# EasyEDAproject_AngstromIO_Mini_Devboard_.net
KiCad netlist of a schematic drawn in EasyEDA Pro
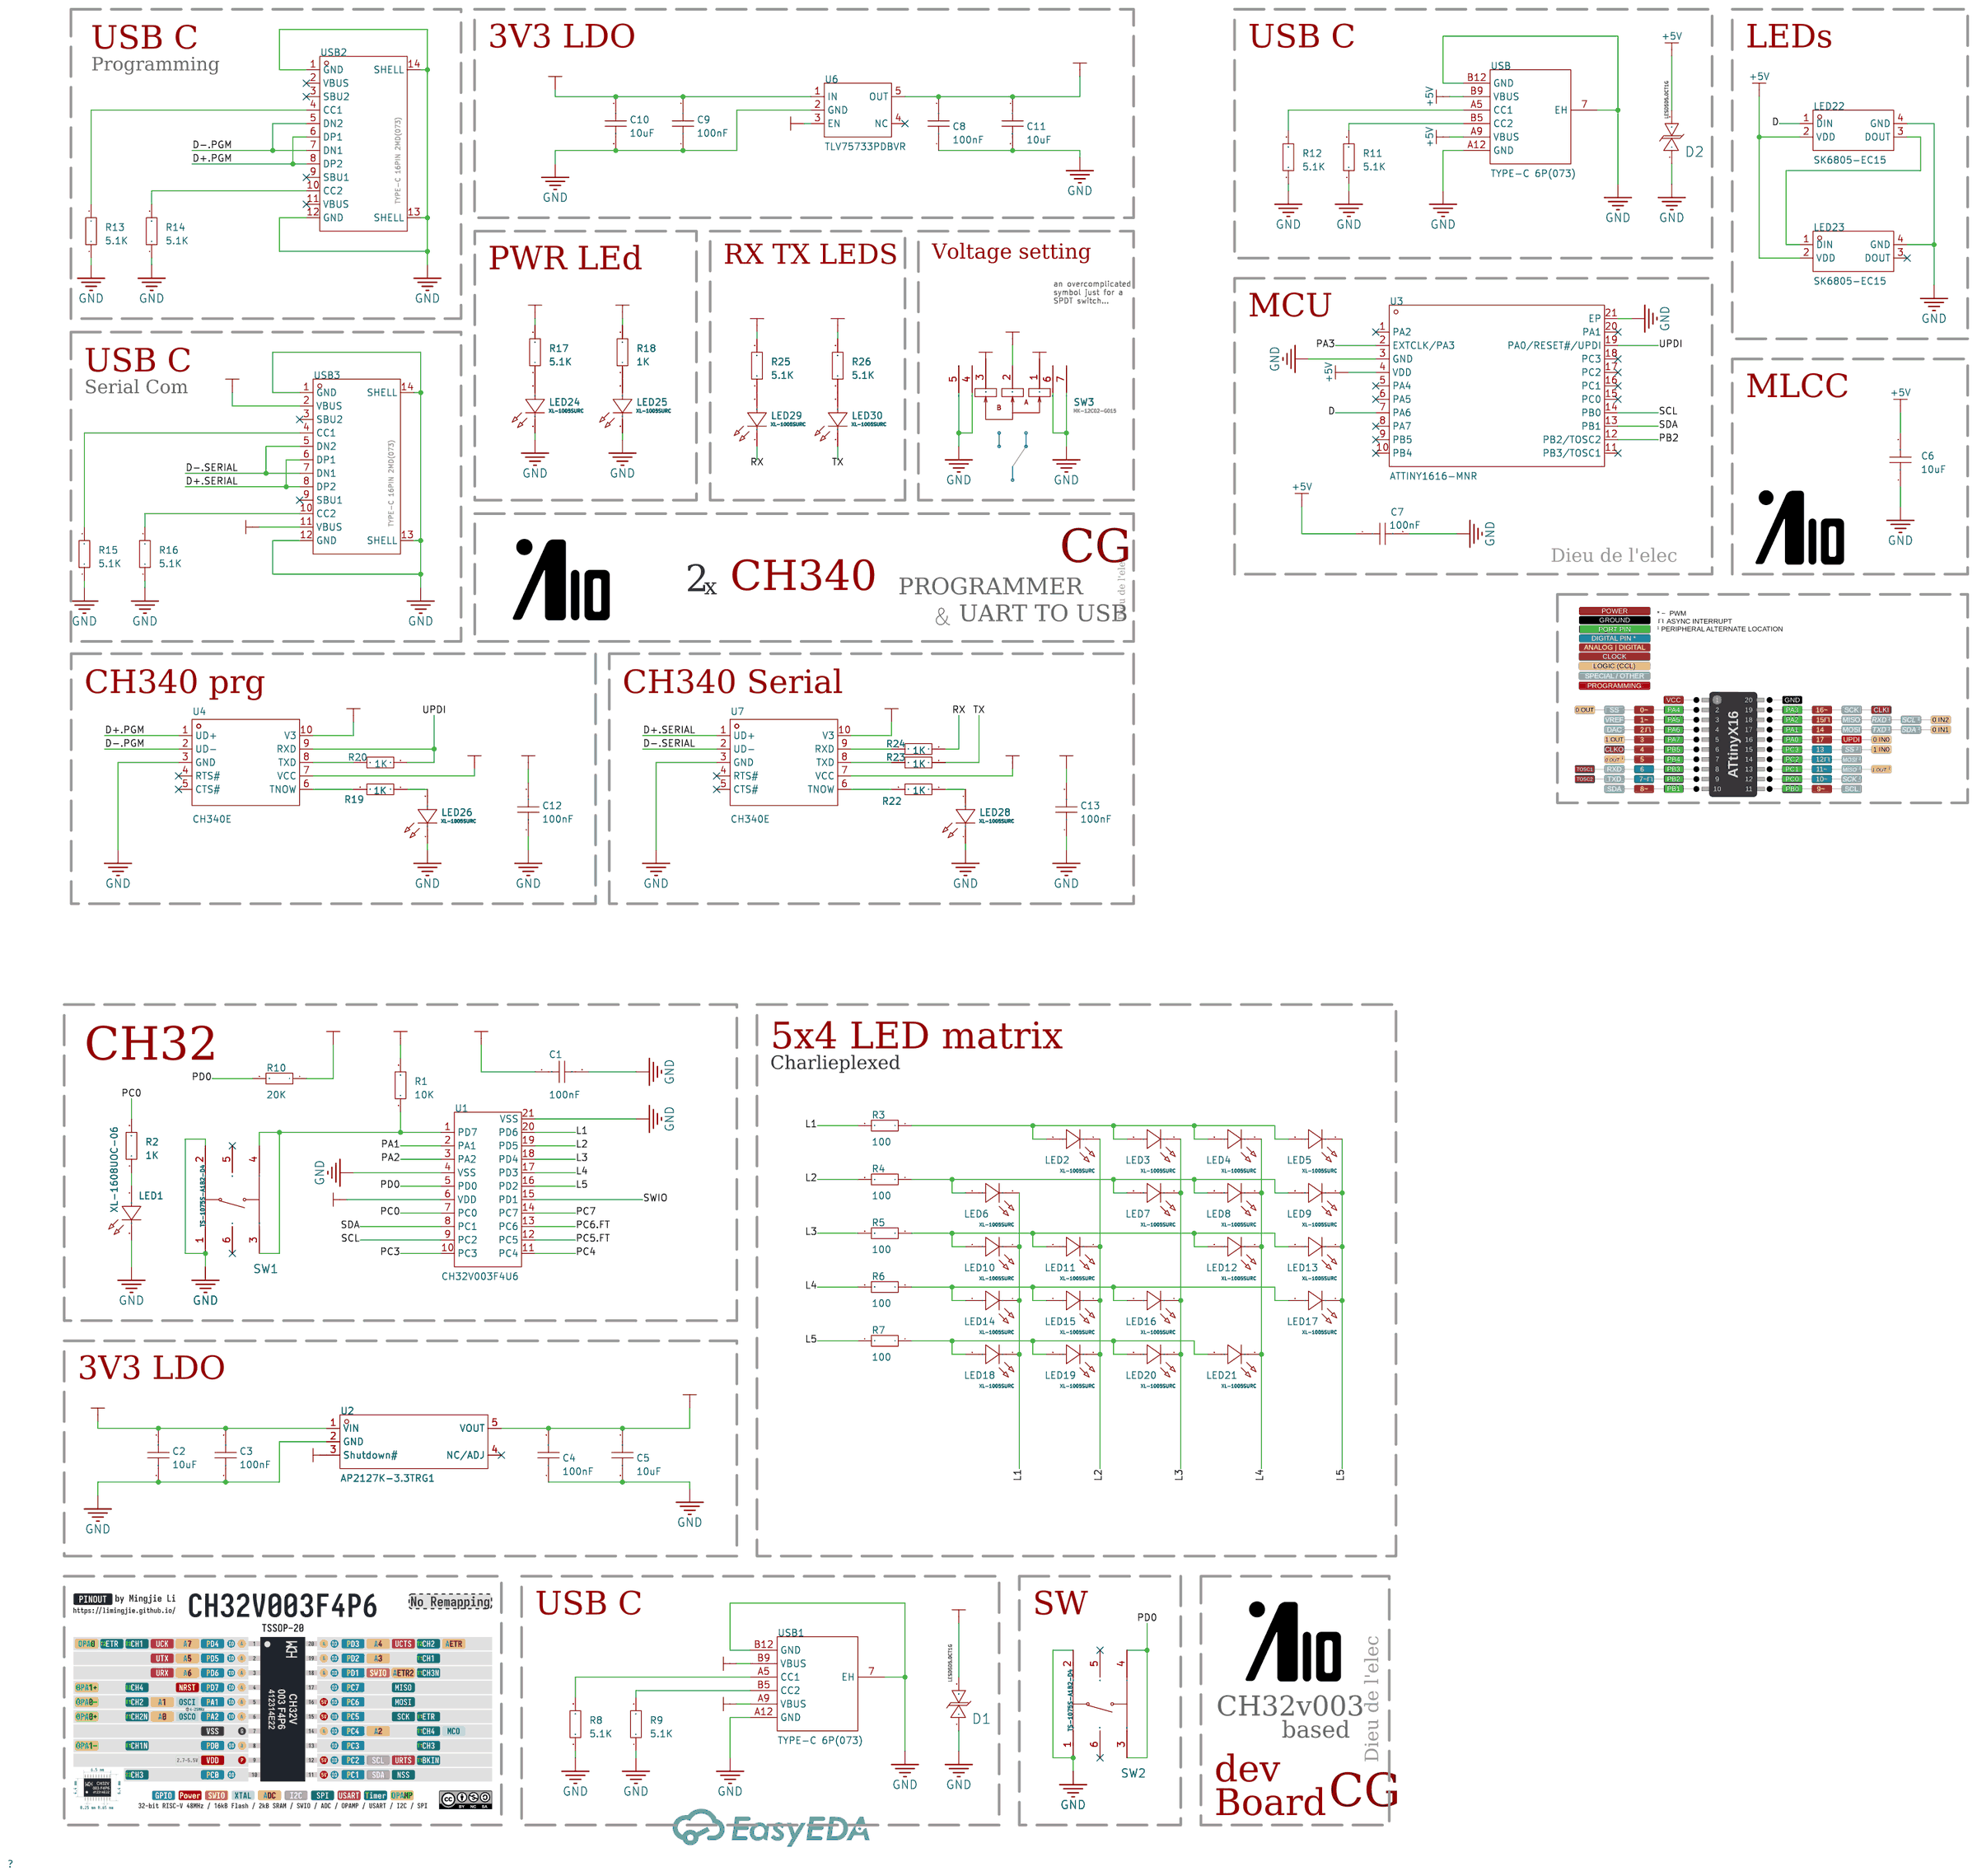
[diagram p0: schematic sheet]

(export (version "E")
  (design (tool "Eeschema 10.0.6"))
  (components
    (comp (ref "C1")
      (value "100nF")
      (footprint "easyedapro:C0805")
      (description "Capacitance:100nF Tolerance:±10% Tolerance:±10% Voltage Rating:16V Temperature Coefficient:X7R")
      (fields
        (field (name "Manufacturer Part") "CL10B104KO8NNNC")
        (field (name "Manufacturer") "SAMSUNG(三星)")
      )
      (libsource (lib "easyedapro") (part "CAP"))
    )
    (comp (ref "C2")
      (value "10uF")
      (footprint "easyedapro:C0805")
      (libsource (lib "easyedapro") (part "CAP"))
    )
    (comp (ref "C3")
      (value "100nF")
      (footprint "easyedapro:C0805")
      (description "Capacitance:100nF Tolerance:±10% Tolerance:±10% Voltage Rating:16V Temperature Coefficient:X7R")
      (fields
        (field (name "Manufacturer Part") "CL10B104KO8NNNC")
        (field (name "Manufacturer") "SAMSUNG(三星)")
      )
      (libsource (lib "easyedapro") (part "CAP"))
    )
    (comp (ref "C4")
      (value "100nF")
      (footprint "easyedapro:C0805")
      (description "Capacitance:100nF Tolerance:±10% Tolerance:±10% Voltage Rating:16V Temperature Coefficient:X7R")
      (fields
        (field (name "Manufacturer Part") "CL10B104KO8NNNC")
        (field (name "Manufacturer") "SAMSUNG(三星)")
      )
      (libsource (lib "easyedapro") (part "CAP"))
    )
    (comp (ref "C5")
      (value "10uF")
      (footprint "easyedapro:C0805")
      (libsource (lib "easyedapro") (part "CAP"))
    )
    (comp (ref "C6")
      (value "10uF")
      (footprint "easyedapro:C0402")
      (description "Capacitance:10uF Tolerance:±20% Tolerance:±20% Voltage Rating:10V Temperature Coefficient:X5R")
      (fields
        (field (name "Manufacturer Part") "CL05A106MP5NUNC")
        (field (name "Manufacturer") "SAMSUNG(三星)")
      )
      (libsource (lib "easyedapro") (part "CL05A106MP5NUNC_C315248"))
    )
    (comp (ref "C7")
      (value "100nF")
      (footprint "easyedapro:C0402")
      (description "Capacitance:100nF Tolerance:±10% Tolerance:±10% Voltage Rating:16V Temperature Coefficient:X7R")
      (fields
        (field (name "Manufacturer Part") "CL05B104KO5NNNC")
        (field (name "Manufacturer") "SAMSUNG(三星)")
      )
      (libsource (lib "easyedapro") (part "CL05B104KO5NNNC"))
    )
    (comp (ref "C8")
      (value "100nF")
      (footprint "easyedapro:C0805")
      (description "Capacitance:100nF Tolerance:±10% Tolerance:±10% Voltage Rating:16V Temperature Coefficient:X7R")
      (fields
        (field (name "Manufacturer Part") "CL10B104KO8NNNC")
        (field (name "Manufacturer") "SAMSUNG(三星)")
      )
      (libsource (lib "easyedapro") (part "CAP"))
    )
    (comp (ref "C9")
      (value "100nF")
      (footprint "easyedapro:C0805")
      (description "Capacitance:100nF Tolerance:±10% Tolerance:±10% Voltage Rating:16V Temperature Coefficient:X7R")
      (fields
        (field (name "Manufacturer Part") "CL10B104KO8NNNC")
        (field (name "Manufacturer") "SAMSUNG(三星)")
      )
      (libsource (lib "easyedapro") (part "CAP"))
    )
    (comp (ref "C10")
      (value "10uF")
      (footprint "easyedapro:C0805")
      (libsource (lib "easyedapro") (part "CAP"))
    )
    (comp (ref "C11")
      (value "10uF")
      (footprint "easyedapro:C0805")
      (libsource (lib "easyedapro") (part "CAP"))
    )
    (comp (ref "C12")
      (value "100nF")
      (footprint "easyedapro:C0805")
      (description "Capacitance:100nF Tolerance:±10% Tolerance:±10% Voltage Rating:16V Temperature Coefficient:X7R")
      (fields
        (field (name "Manufacturer Part") "CL10B104KO8NNNC")
        (field (name "Manufacturer") "SAMSUNG(三星)")
      )
      (libsource (lib "easyedapro") (part "CAP"))
    )
    (comp (ref "C13")
      (value "100nF")
      (footprint "easyedapro:C0805")
      (description "Capacitance:100nF Tolerance:±10% Tolerance:±10% Voltage Rating:16V Temperature Coefficient:X7R")
      (fields
        (field (name "Manufacturer Part") "CL10B104KO8NNNC")
        (field (name "Manufacturer") "SAMSUNG(三星)")
      )
      (libsource (lib "easyedapro") (part "CAP"))
    )
    (comp (ref "D1")
      (value "LESD5D5.0CT1G")
      (footprint "easyedapro:SOD-523_L1.2-W0.8-LS1.6-BI")
      (fields (field (name "Manufacturer") "UMW(友台半导体)"))
      (libsource (lib "easyedapro") (part "LESD5D5.0CT1G_C5199850"))
    )
    (comp (ref "D2")
      (value "LESD5D5.0CT1G")
      (footprint "easyedapro:SOD-523_L1.2-W0.8-LS1.6-BI")
      (fields (field (name "Manufacturer") "UMW(友台半导体)"))
      (libsource (lib "easyedapro") (part "LESD5D5.0CT1G_C5199850"))
    )
    (comp (ref "LED1")
      (value "XL-1608UOC-06")
      (footprint "easyedapro:LED0603-R-RD_ORANGE")
      (fields (field (name "Manufacturer") "XINGLIGHT(成兴光)"))
      (libsource (lib "easyedapro") (part "XL-1608UOC-06"))
    )
    (comp (ref "LED2")
      (value "XL-1005SURC")
      (footprint "easyedapro:LED0402-RD")
      (fields (field (name "Manufacturer") "XINGLIGHT(成兴光)"))
      (libsource (lib "easyedapro") (part "XL-1005SURC_C25503345"))
    )
    (comp (ref "LED3")
      (value "XL-1005SURC")
      (footprint "easyedapro:LED0402-RD")
      (fields (field (name "Manufacturer") "XINGLIGHT(成兴光)"))
      (libsource (lib "easyedapro") (part "XL-1005SURC_C25503345"))
    )
    (comp (ref "LED4")
      (value "XL-1005SURC")
      (footprint "easyedapro:LED0402-RD")
      (fields (field (name "Manufacturer") "XINGLIGHT(成兴光)"))
      (libsource (lib "easyedapro") (part "XL-1005SURC_C25503345"))
    )
    (comp (ref "LED5")
      (value "XL-1005SURC")
      (footprint "easyedapro:LED0402-RD")
      (fields (field (name "Manufacturer") "XINGLIGHT(成兴光)"))
      (libsource (lib "easyedapro") (part "XL-1005SURC_C25503345"))
    )
    (comp (ref "LED6")
      (value "XL-1005SURC")
      (footprint "easyedapro:LED0402-RD")
      (fields (field (name "Manufacturer") "XINGLIGHT(成兴光)"))
      (libsource (lib "easyedapro") (part "XL-1005SURC_C25503345"))
    )
    (comp (ref "LED7")
      (value "XL-1005SURC")
      (footprint "easyedapro:LED0402-RD")
      (fields (field (name "Manufacturer") "XINGLIGHT(成兴光)"))
      (libsource (lib "easyedapro") (part "XL-1005SURC_C25503345"))
    )
    (comp (ref "LED8")
      (value "XL-1005SURC")
      (footprint "easyedapro:LED0402-RD")
      (fields (field (name "Manufacturer") "XINGLIGHT(成兴光)"))
      (libsource (lib "easyedapro") (part "XL-1005SURC_C25503345"))
    )
    (comp (ref "LED9")
      (value "XL-1005SURC")
      (footprint "easyedapro:LED0402-RD")
      (fields (field (name "Manufacturer") "XINGLIGHT(成兴光)"))
      (libsource (lib "easyedapro") (part "XL-1005SURC_C25503345"))
    )
    (comp (ref "LED10")
      (value "XL-1005SURC")
      (footprint "easyedapro:LED0402-RD")
      (fields (field (name "Manufacturer") "XINGLIGHT(成兴光)"))
      (libsource (lib "easyedapro") (part "XL-1005SURC_C25503345"))
    )
    (comp (ref "LED11")
      (value "XL-1005SURC")
      (footprint "easyedapro:LED0402-RD")
      (fields (field (name "Manufacturer") "XINGLIGHT(成兴光)"))
      (libsource (lib "easyedapro") (part "XL-1005SURC_C25503345"))
    )
    (comp (ref "LED12")
      (value "XL-1005SURC")
      (footprint "easyedapro:LED0402-RD")
      (fields (field (name "Manufacturer") "XINGLIGHT(成兴光)"))
      (libsource (lib "easyedapro") (part "XL-1005SURC_C25503345"))
    )
    (comp (ref "LED13")
      (value "XL-1005SURC")
      (footprint "easyedapro:LED0402-RD")
      (fields (field (name "Manufacturer") "XINGLIGHT(成兴光)"))
      (libsource (lib "easyedapro") (part "XL-1005SURC_C25503345"))
    )
    (comp (ref "LED14")
      (value "XL-1005SURC")
      (footprint "easyedapro:LED0402-RD")
      (fields (field (name "Manufacturer") "XINGLIGHT(成兴光)"))
      (libsource (lib "easyedapro") (part "XL-1005SURC_C25503345"))
    )
    (comp (ref "LED15")
      (value "XL-1005SURC")
      (footprint "easyedapro:LED0402-RD")
      (fields (field (name "Manufacturer") "XINGLIGHT(成兴光)"))
      (libsource (lib "easyedapro") (part "XL-1005SURC_C25503345"))
    )
    (comp (ref "LED16")
      (value "XL-1005SURC")
      (footprint "easyedapro:LED0402-RD")
      (fields (field (name "Manufacturer") "XINGLIGHT(成兴光)"))
      (libsource (lib "easyedapro") (part "XL-1005SURC_C25503345"))
    )
    (comp (ref "LED17")
      (value "XL-1005SURC")
      (footprint "easyedapro:LED0402-RD")
      (fields (field (name "Manufacturer") "XINGLIGHT(成兴光)"))
      (libsource (lib "easyedapro") (part "XL-1005SURC_C25503345"))
    )
    (comp (ref "LED18")
      (value "XL-1005SURC")
      (footprint "easyedapro:LED0402-RD")
      (fields (field (name "Manufacturer") "XINGLIGHT(成兴光)"))
      (libsource (lib "easyedapro") (part "XL-1005SURC_C25503345"))
    )
    (comp (ref "LED19")
      (value "XL-1005SURC")
      (footprint "easyedapro:LED0402-RD")
      (fields (field (name "Manufacturer") "XINGLIGHT(成兴光)"))
      (libsource (lib "easyedapro") (part "XL-1005SURC_C25503345"))
    )
    (comp (ref "LED20")
      (value "XL-1005SURC")
      (footprint "easyedapro:LED0402-RD")
      (fields (field (name "Manufacturer") "XINGLIGHT(成兴光)"))
      (libsource (lib "easyedapro") (part "XL-1005SURC_C25503345"))
    )
    (comp (ref "LED21")
      (value "XL-1005SURC")
      (footprint "easyedapro:LED0402-RD")
      (fields (field (name "Manufacturer") "XINGLIGHT(成兴光)"))
      (libsource (lib "easyedapro") (part "XL-1005SURC_C25503345"))
    )
    (comp (ref "LED22")
      (value "SK6805-EC15")
      (footprint "easyedapro:LED-SMD_4P-L1.5-W1.5-BL")
      (fields (field (name "Manufacturer") "欧思科光电"))
      (libsource (lib "easyedapro") (part "SK6805-EC15"))
    )
    (comp (ref "LED23")
      (value "SK6805-EC15")
      (footprint "easyedapro:LED-SMD_4P-L1.5-W1.5-BL")
      (fields (field (name "Manufacturer") "欧思科光电"))
      (libsource (lib "easyedapro") (part "SK6805-EC15"))
    )
    (comp (ref "LED24")
      (value "XL-1005SURC")
      (footprint "easyedapro:LED0402-RD")
      (fields (field (name "Manufacturer") "XINGLIGHT(成兴光)"))
      (libsource (lib "easyedapro") (part "XL-1005SURC_C25503345"))
    )
    (comp (ref "LED25")
      (value "XL-1005SURC")
      (footprint "easyedapro:LED0402-RD")
      (fields (field (name "Manufacturer") "XINGLIGHT(成兴光)"))
      (libsource (lib "easyedapro") (part "XL-1005SURC_C25503345"))
    )
    (comp (ref "LED26")
      (value "XL-1005SURC")
      (footprint "easyedapro:LED0402-RD")
      (fields (field (name "Manufacturer") "XINGLIGHT(成兴光)"))
      (libsource (lib "easyedapro") (part "XL-1005SURC_C25503345"))
    )
    (comp (ref "LED28")
      (value "XL-1005SURC")
      (footprint "easyedapro:LED0402-RD")
      (fields (field (name "Manufacturer") "XINGLIGHT(成兴光)"))
      (libsource (lib "easyedapro") (part "XL-1005SURC_C25503345"))
    )
    (comp (ref "LED29")
      (value "XL-1005SURC")
      (footprint "easyedapro:LED0402-RD")
      (fields (field (name "Manufacturer") "XINGLIGHT(成兴光)"))
      (libsource (lib "easyedapro") (part "XL-1005SURC_C25503345"))
    )
    (comp (ref "LED30")
      (value "XL-1005SURC")
      (footprint "easyedapro:LED0402-RD")
      (fields (field (name "Manufacturer") "XINGLIGHT(成兴光)"))
      (libsource (lib "easyedapro") (part "XL-1005SURC_C25503345"))
    )
    (comp (ref "R1") (value "10K") (footprint "easyedapro:R0402") (libsource (lib "easyedapro") (part "Res")))
    (comp (ref "R2") (value "1K") (footprint "easyedapro:R0402") (libsource (lib "easyedapro") (part "Res")))
    (comp (ref "R3") (value "100") (footprint "easyedapro:R0402") (libsource (lib "easyedapro") (part "Res")))
    (comp (ref "R4") (value "100") (footprint "easyedapro:R0402") (libsource (lib "easyedapro") (part "Res")))
    (comp (ref "R5") (value "100") (footprint "easyedapro:R0402") (libsource (lib "easyedapro") (part "Res")))
    (comp (ref "R6") (value "100") (footprint "easyedapro:R0402") (libsource (lib "easyedapro") (part "Res")))
    (comp (ref "R7") (value "100") (footprint "easyedapro:R0402") (libsource (lib "easyedapro") (part "Res")))
    (comp (ref "R8")
      (value "5.1K")
      (footprint "easyedapro:R0402")
      (libsource (lib "easyedapro") (part "Res"))
    )
    (comp (ref "R9")
      (value "5.1K")
      (footprint "easyedapro:R0402")
      (libsource (lib "easyedapro") (part "Res"))
    )
    (comp (ref "R10")
      (value "20K")
      (footprint "easyedapro:R0402")
      (libsource (lib "easyedapro") (part "Res"))
    )
    (comp (ref "R11")
      (value "5.1K")
      (footprint "easyedapro:R0402")
      (libsource (lib "easyedapro") (part "Res"))
    )
    (comp (ref "R12")
      (value "5.1K")
      (footprint "easyedapro:R0402")
      (libsource (lib "easyedapro") (part "Res"))
    )
    (comp (ref "R13")
      (value "5.1K")
      (footprint "easyedapro:R0402")
      (libsource (lib "easyedapro") (part "Res"))
    )
    (comp (ref "R14")
      (value "5.1K")
      (footprint "easyedapro:R0402")
      (libsource (lib "easyedapro") (part "Res"))
    )
    (comp (ref "R15")
      (value "5.1K")
      (footprint "easyedapro:R0402")
      (libsource (lib "easyedapro") (part "Res"))
    )
    (comp (ref "R16")
      (value "5.1K")
      (footprint "easyedapro:R0402")
      (libsource (lib "easyedapro") (part "Res"))
    )
    (comp (ref "R17")
      (value "5.1K")
      (footprint "easyedapro:R0402")
      (libsource (lib "easyedapro") (part "Res"))
    )
    (comp (ref "R18") (value "1K") (footprint "easyedapro:R0402") (libsource (lib "easyedapro") (part "Res")))
    (comp (ref "R19") (value "1K") (footprint "easyedapro:R0402") (libsource (lib "easyedapro") (part "Res")))
    (comp (ref "R20") (value "1K") (footprint "easyedapro:R0402") (libsource (lib "easyedapro") (part "Res")))
    (comp (ref "R22") (value "1K") (footprint "easyedapro:R0402") (libsource (lib "easyedapro") (part "Res")))
    (comp (ref "R23") (value "1K") (footprint "easyedapro:R0402") (libsource (lib "easyedapro") (part "Res")))
    (comp (ref "R24") (value "1K") (footprint "easyedapro:R0402") (libsource (lib "easyedapro") (part "Res")))
    (comp (ref "R25")
      (value "5.1K")
      (footprint "easyedapro:R0402")
      (libsource (lib "easyedapro") (part "Res"))
    )
    (comp (ref "R26")
      (value "5.1K")
      (footprint "easyedapro:R0402")
      (libsource (lib "easyedapro") (part "Res"))
    )
    (comp (ref "SW1")
      (value "TS-1075S-A1B2-D4")
      (footprint "easyedapro:SW-SMD_4P-L3.1-W3.1-P2.20-LS4.0")
      (fields (field (name "Manufacturer") "Yuandi(元迪)"))
      (libsource (lib "easyedapro") (part "TS-1075S-A1B2-D4"))
    )
    (comp (ref "SW2")
      (value "TS-1075S-A1B2-D4")
      (footprint "easyedapro:SW-SMD_4P-L3.1-W3.1-P2.20-LS4.0")
      (fields (field (name "Manufacturer") "Yuandi(元迪)"))
      (libsource (lib "easyedapro") (part "TS-1075S-A1B2-D4"))
    )
    (comp (ref "SW3")
      (value "MK-12C02-G015")
      (footprint "easyedapro:SW-SMD_G-SWITCH_MK-12C02-G015")
      (fields (field (name "Manufacturer") "G-Switch(品赞)"))
      (libsource (lib "easyedapro") (part "MK-12C02-G015"))
    )
    (comp (ref "U1")
      (value "CH32V003F4U6")
      (footprint "easyedapro:QFN-20_L3.0-W3.0-P0.40-TL-EP1.7")
      (description "CPU Core:RISC-V CPU Maximum Speed:48MHz Program Storage Size:16KB Number of I/O:18 Applications:-")
      (fields (field (name "Manufacturer") "WCH(南京沁恒)"))
      (libsource (lib "easyedapro") (part "CH32V003F4U6"))
    )
    (comp (ref "U2")
      (value "AP2127K-3.3TRG1")
      (footprint "easyedapro:SOT-23-5_L3.0-W1.7-P0.95-LS2.8-BR")
      (fields (field (name "Manufacturer") "DIODES(美台)"))
      (libsource (lib "easyedapro") (part "AP2127K-3.3TRG1"))
    )
    (comp (ref "U3")
      (value "ATTINY1616-MNR")
      (footprint "easyedapro:QFN-20_L3.0-W3.0-P0.40-BL-EP1.7")
      (fields (field (name "Manufacturer") "MICROCHIP(美国微芯)"))
      (libsource (lib "easyedapro") (part "ATTINY1616-MNR"))
    )
    (comp (ref "U4")
      (value "CH340E")
      (footprint "easyedapro:MSOP-10_L3.0-W3.0-P0.50-LS5.0-BL")
      (fields (field (name "Manufacturer") "WCH(南京沁恒)"))
      (libsource (lib "easyedapro") (part "CH340E"))
    )
    (comp (ref "U6")
      (value "TLV75733PDBVR")
      (footprint "easyedapro:SOT-23-5_L2.9-W1.6-P0.95-LS2.8-BL")
      (fields (field (name "Manufacturer") "TI(德州仪器)"))
      (libsource (lib "easyedapro") (part "TLV75733PDBVR"))
    )
    (comp (ref "U7")
      (value "CH340E")
      (footprint "easyedapro:MSOP-10_L3.0-W3.0-P0.50-LS5.0-BL")
      (fields (field (name "Manufacturer") "WCH(南京沁恒)"))
      (libsource (lib "easyedapro") (part "CH340E"))
    )
    (comp (ref "USB")
      (value "TYPE-C 6P(073)")
      (footprint "easyedapro:TYPE-C-SMD_TYPE-C-6P-073")
      (fields (field (name "Manufacturer") "SHOU HAN(首韩)"))
      (libsource (lib "easyedapro") (part "TYPE-C 6P(073)"))
    )
    (comp (ref "USB1")
      (value "TYPE-C 6P(073)")
      (footprint "easyedapro:TYPE-C-SMD_TYPE-C-6P-073")
      (fields (field (name "Manufacturer") "SHOU HAN(首韩)"))
      (libsource (lib "easyedapro") (part "TYPE-C 6P(073)"))
    )
    (comp (ref "USB2")
      (value "TYPE-C 16PIN 2MD(073)")
      (footprint "easyedapro:USB-C-SMD_TYPE-C-6PIN-2MD-073")
      (fields (field (name "Manufacturer") "SHOU HAN(首韩)"))
      (libsource (lib "easyedapro") (part "TYPE-C 16PIN 2MD(073)"))
    )
    (comp (ref "USB3")
      (value "TYPE-C 16PIN 2MD(073)")
      (footprint "easyedapro:USB-C-SMD_TYPE-C-6PIN-2MD-073")
      (fields (field (name "Manufacturer") "SHOU HAN(首韩)"))
      (libsource (lib "easyedapro") (part "TYPE-C 16PIN 2MD(073)"))
    )
  )
  (nets
    (net (code "1") (name "+3.3V") (class "Default")
      (node (ref "C1") (pin "1") (pinfunction "1_1") (pintype "input"))
      (node (ref "C11") (pin "1") (pinfunction "1_1") (pintype "input"))
      (node (ref "C4") (pin "2") (pinfunction "2_2") (pintype "input"))
      (node (ref "C5") (pin "1") (pinfunction "1_1") (pintype "input"))
      (node (ref "C8") (pin "2") (pinfunction "2_2") (pintype "input"))
      (node (ref "R1") (pin "2") (pinfunction "2_2") (pintype "input"))
      (node (ref "R10") (pin "1") (pinfunction "1_1") (pintype "input"))
      (node (ref "R18") (pin "2") (pinfunction "2_2") (pintype "input"))
      (node (ref "R25") (pin "2") (pinfunction "2_2") (pintype "input"))
      (node (ref "R26") (pin "2") (pinfunction "2_2") (pintype "input"))
      (node (ref "SW3") (pin "1") (pinfunction "1_1") (pintype "unspecified"))
      (node (ref "U1") (pin "6") (pinfunction "VDD_6") (pintype "unspecified"))
      (node (ref "U2") (pin "5") (pinfunction "VOUT_5") (pintype "unspecified"))
      (node (ref "U4") (pin "10") (pinfunction "V3_10") (pintype "unspecified"))
      (node (ref "U6") (pin "5") (pinfunction "OUT_5") (pintype "unspecified"))
      (node (ref "U7") (pin "10") (pinfunction "V3_10") (pintype "unspecified"))
    )
    (net (code "2") (name "+5V") (class "Default")
      (node (ref "C6") (pin "2") (pinfunction "2_2") (pintype "unspecified"))
      (node (ref "C7") (pin "1") (pinfunction "1_1") (pintype "unspecified"))
      (node (ref "D2") (pin "2") (pinfunction "2_2") (pintype "unspecified"))
      (node (ref "LED22") (pin "2") (pinfunction "VDD_2") (pintype "unspecified"))
      (node (ref "LED23") (pin "2") (pinfunction "VDD_2") (pintype "unspecified"))
      (node (ref "U3") (pin "4") (pinfunction "VDD_4") (pintype "unspecified"))
      (node (ref "USB") (pin "A9") (pinfunction "VBUS_A9") (pintype "unspecified"))
      (node (ref "USB") (pin "B9") (pinfunction "VBUS_B9") (pintype "unspecified"))
    )
    (net (code "3") (name "/D") (class "Default")
      (node (ref "LED22") (pin "1") (pinfunction "DIN_1") (pintype "unspecified"))
      (node (ref "U3") (pin "7") (pinfunction "PA6_7") (pintype "unspecified"))
    )
    (net (code "4") (name "/D+.PGM") (class "Default")
      (node (ref "U4") (pin "1") (pinfunction "UD+_1") (pintype "unspecified"))
      (node (ref "USB2") (pin "6") (pinfunction "DP1_6") (pintype "unspecified"))
      (node (ref "USB2") (pin "8") (pinfunction "DP2_8") (pintype "unspecified"))
    )
    (net (code "5") (name "/D+.SERIAL") (class "Default")
      (node (ref "U7") (pin "1") (pinfunction "UD+_1") (pintype "unspecified"))
      (node (ref "USB3") (pin "6") (pinfunction "DP1_6") (pintype "unspecified"))
      (node (ref "USB3") (pin "8") (pinfunction "DP2_8") (pintype "unspecified"))
    )
    (net (code "6") (name "/D-.PGM") (class "Default")
      (node (ref "U4") (pin "2") (pinfunction "UD-_2") (pintype "unspecified"))
      (node (ref "USB2") (pin "5") (pinfunction "DN2_5") (pintype "unspecified"))
      (node (ref "USB2") (pin "7") (pinfunction "DN1_7") (pintype "unspecified"))
    )
    (net (code "7") (name "/D-.SERIAL") (class "Default")
      (node (ref "U7") (pin "2") (pinfunction "UD-_2") (pintype "unspecified"))
      (node (ref "USB3") (pin "5") (pinfunction "DN2_5") (pintype "unspecified"))
      (node (ref "USB3") (pin "7") (pinfunction "DN1_7") (pintype "unspecified"))
    )
    (net (code "8") (name "/L1") (class "Default")
      (node (ref "LED10") (pin "1") (pinfunction "K_1") (pintype "unspecified"))
      (node (ref "LED14") (pin "1") (pinfunction "K_1") (pintype "unspecified"))
      (node (ref "LED18") (pin "1") (pinfunction "K_1") (pintype "unspecified"))
      (node (ref "LED6") (pin "1") (pinfunction "K_1") (pintype "unspecified"))
      (node (ref "R3") (pin "2") (pinfunction "2_2") (pintype "input"))
      (node (ref "U1") (pin "20") (pinfunction "PD6_20") (pintype "unspecified"))
    )
    (net (code "9") (name "/L2") (class "Default")
      (node (ref "LED11") (pin "1") (pinfunction "K_1") (pintype "unspecified"))
      (node (ref "LED15") (pin "1") (pinfunction "K_1") (pintype "unspecified"))
      (node (ref "LED19") (pin "1") (pinfunction "K_1") (pintype "unspecified"))
      (node (ref "LED2") (pin "1") (pinfunction "K_1") (pintype "unspecified"))
      (node (ref "R4") (pin "2") (pinfunction "2_2") (pintype "input"))
      (node (ref "U1") (pin "19") (pinfunction "PD5_19") (pintype "unspecified"))
    )
    (net (code "10") (name "/L3") (class "Default")
      (node (ref "LED16") (pin "1") (pinfunction "K_1") (pintype "unspecified"))
      (node (ref "LED20") (pin "1") (pinfunction "K_1") (pintype "unspecified"))
      (node (ref "LED3") (pin "1") (pinfunction "K_1") (pintype "unspecified"))
      (node (ref "LED7") (pin "1") (pinfunction "K_1") (pintype "unspecified"))
      (node (ref "R5") (pin "2") (pinfunction "2_2") (pintype "input"))
      (node (ref "U1") (pin "18") (pinfunction "PD4_18") (pintype "unspecified"))
    )
    (net (code "11") (name "/L4") (class "Default")
      (node (ref "LED12") (pin "1") (pinfunction "K_1") (pintype "unspecified"))
      (node (ref "LED21") (pin "1") (pinfunction "K_1") (pintype "unspecified"))
      (node (ref "LED4") (pin "1") (pinfunction "K_1") (pintype "unspecified"))
      (node (ref "LED8") (pin "1") (pinfunction "K_1") (pintype "unspecified"))
      (node (ref "R6") (pin "2") (pinfunction "2_2") (pintype "input"))
      (node (ref "U1") (pin "17") (pinfunction "PD3_17") (pintype "unspecified"))
    )
    (net (code "12") (name "/L5") (class "Default")
      (node (ref "LED13") (pin "1") (pinfunction "K_1") (pintype "unspecified"))
      (node (ref "LED17") (pin "1") (pinfunction "K_1") (pintype "unspecified"))
      (node (ref "LED5") (pin "1") (pinfunction "K_1") (pintype "unspecified"))
      (node (ref "LED9") (pin "1") (pinfunction "K_1") (pintype "unspecified"))
      (node (ref "R7") (pin "2") (pinfunction "2_2") (pintype "input"))
      (node (ref "U1") (pin "16") (pinfunction "PD2_16") (pintype "unspecified"))
    )
    (net (code "13") (name "/PA1") (class "Default")
      (node (ref "U1") (pin "2") (pinfunction "PA1_2") (pintype "unspecified"))
    )
    (net (code "14") (name "/PA2") (class "Default")
      (node (ref "U1") (pin "3") (pinfunction "PA2_3") (pintype "unspecified"))
    )
    (net (code "15") (name "/PA3") (class "Default")
      (node (ref "U3") (pin "2") (pinfunction "EXTCLK/PA3_2") (pintype "unspecified"))
    )
    (net (code "16") (name "/PB2") (class "Default")
      (node (ref "U3") (pin "12") (pinfunction "PB2/TOSC2_12") (pintype "unspecified"))
    )
    (net (code "17") (name "/PC0") (class "Default")
      (node (ref "R2") (pin "2") (pinfunction "2_2") (pintype "input"))
      (node (ref "U1") (pin "7") (pinfunction "PC0_7") (pintype "unspecified"))
    )
    (net (code "18") (name "/PC3") (class "Default")
      (node (ref "U1") (pin "10") (pinfunction "PC3_10") (pintype "unspecified"))
    )
    (net (code "19") (name "/PC4") (class "Default")
      (node (ref "U1") (pin "11") (pinfunction "PC4_11") (pintype "unspecified"))
    )
    (net (code "20") (name "/PC5.FT") (class "Default")
      (node (ref "U1") (pin "12") (pinfunction "PC5_12") (pintype "unspecified"))
    )
    (net (code "21") (name "/PC6.FT") (class "Default")
      (node (ref "U1") (pin "13") (pinfunction "PC6_13") (pintype "unspecified"))
    )
    (net (code "22") (name "/PC7") (class "Default")
      (node (ref "U1") (pin "14") (pinfunction "PC7_14") (pintype "unspecified"))
    )
    (net (code "23") (name "/PD0") (class "Default")
      (node (ref "R10") (pin "2") (pinfunction "2_2") (pintype "input"))
      (node (ref "SW2") (pin "3") (pinfunction "3_3") (pintype "input"))
      (node (ref "SW2") (pin "4") (pinfunction "4_4") (pintype "input"))
      (node (ref "U1") (pin "5") (pinfunction "PD0_5") (pintype "unspecified"))
    )
    (net (code "24") (name "/RX") (class "Default")
      (node (ref "LED29") (pin "1") (pinfunction "K_1") (pintype "unspecified"))
      (node (ref "R24") (pin "1") (pinfunction "1_1") (pintype "input"))
    )
    (net (code "25") (name "/SCL") (class "Default")
      (node (ref "U1") (pin "9") (pinfunction "PC2_9") (pintype "unspecified"))
      (node (ref "U3") (pin "14") (pinfunction "PB0_14") (pintype "unspecified"))
    )
    (net (code "26") (name "/SDA") (class "Default")
      (node (ref "U1") (pin "8") (pinfunction "PC1_8") (pintype "unspecified"))
      (node (ref "U3") (pin "13") (pinfunction "PB1_13") (pintype "unspecified"))
    )
    (net (code "27") (name "/SWIO") (class "Default")
      (node (ref "U1") (pin "15") (pinfunction "PD1_15") (pintype "unspecified"))
    )
    (net (code "28") (name "/TX") (class "Default")
      (node (ref "LED30") (pin "1") (pinfunction "K_1") (pintype "unspecified"))
      (node (ref "R23") (pin "1") (pinfunction "1_1") (pintype "input"))
    )
    (net (code "29") (name "/UPDI") (class "Default")
      (node (ref "R20") (pin "1") (pinfunction "1_1") (pintype "input"))
      (node (ref "U3") (pin "19") (pinfunction "PA0/RESET#/UPDI_19") (pintype "unspecified"))
      (node (ref "U4") (pin "9") (pinfunction "RXD_9") (pintype "unspecified"))
    )
    (net (code "30") (name "GND") (class "Default")
      (node (ref "C1") (pin "2") (pinfunction "2_2") (pintype "input"))
      (node (ref "C10") (pin "2") (pinfunction "2_2") (pintype "input"))
      (node (ref "C11") (pin "2") (pinfunction "2_2") (pintype "input"))
      (node (ref "C12") (pin "1") (pinfunction "1_1") (pintype "input"))
      (node (ref "C13") (pin "1") (pinfunction "1_1") (pintype "input"))
      (node (ref "C2") (pin "2") (pinfunction "2_2") (pintype "input"))
      (node (ref "C3") (pin "1") (pinfunction "1_1") (pintype "input"))
      (node (ref "C4") (pin "1") (pinfunction "1_1") (pintype "input"))
      (node (ref "C5") (pin "2") (pinfunction "2_2") (pintype "input"))
      (node (ref "C6") (pin "1") (pinfunction "1_1") (pintype "unspecified"))
      (node (ref "C7") (pin "2") (pinfunction "2_2") (pintype "unspecified"))
      (node (ref "C8") (pin "1") (pinfunction "1_1") (pintype "input"))
      (node (ref "C9") (pin "1") (pinfunction "1_1") (pintype "input"))
      (node (ref "D1") (pin "1") (pinfunction "1_1") (pintype "unspecified"))
      (node (ref "D2") (pin "1") (pinfunction "1_1") (pintype "unspecified"))
      (node (ref "LED1") (pin "2") (pinfunction "A_2") (pintype "unspecified"))
      (node (ref "LED22") (pin "4") (pinfunction "GND_4") (pintype "unspecified"))
      (node (ref "LED23") (pin "4") (pinfunction "GND_4") (pintype "unspecified"))
      (node (ref "LED24") (pin "1") (pinfunction "K_1") (pintype "unspecified"))
      (node (ref "LED25") (pin "1") (pinfunction "K_1") (pintype "unspecified"))
      (node (ref "LED26") (pin "1") (pinfunction "K_1") (pintype "unspecified"))
      (node (ref "LED28") (pin "1") (pinfunction "K_1") (pintype "unspecified"))
      (node (ref "R11") (pin "1") (pinfunction "1_1") (pintype "input"))
      (node (ref "R12") (pin "1") (pinfunction "1_1") (pintype "input"))
      (node (ref "R13") (pin "1") (pinfunction "1_1") (pintype "input"))
      (node (ref "R14") (pin "1") (pinfunction "1_1") (pintype "input"))
      (node (ref "R15") (pin "1") (pinfunction "1_1") (pintype "input"))
      (node (ref "R16") (pin "1") (pinfunction "1_1") (pintype "input"))
      (node (ref "R8") (pin "1") (pinfunction "1_1") (pintype "input"))
      (node (ref "R9") (pin "1") (pinfunction "1_1") (pintype "input"))
      (node (ref "SW1") (pin "1") (pinfunction "1_1") (pintype "input"))
      (node (ref "SW1") (pin "2") (pinfunction "2_2") (pintype "input"))
      (node (ref "SW2") (pin "1") (pinfunction "1_1") (pintype "input"))
      (node (ref "SW2") (pin "2") (pinfunction "2_2") (pintype "input"))
      (node (ref "SW3") (pin "4") (pinfunction "4_4") (pintype "unspecified"))
      (node (ref "SW3") (pin "5") (pinfunction "5_5") (pintype "unspecified"))
      (node (ref "SW3") (pin "6") (pinfunction "6_6") (pintype "unspecified"))
      (node (ref "SW3") (pin "7") (pinfunction "7_7") (pintype "unspecified"))
      (node (ref "U1") (pin "21") (pinfunction "VSS_21") (pintype "unspecified"))
      (node (ref "U1") (pin "4") (pinfunction "VSS_4") (pintype "unspecified"))
      (node (ref "U2") (pin "2") (pinfunction "GND_2") (pintype "unspecified"))
      (node (ref "U3") (pin "21") (pinfunction "EP_21") (pintype "unspecified"))
      (node (ref "U3") (pin "3") (pinfunction "GND_3") (pintype "unspecified"))
      (node (ref "U4") (pin "3") (pinfunction "GND_3") (pintype "unspecified"))
      (node (ref "U6") (pin "2") (pinfunction "GND_2") (pintype "unspecified"))
      (node (ref "U7") (pin "3") (pinfunction "GND_3") (pintype "unspecified"))
      (node (ref "USB") (pin "7") (pinfunction "EH_7") (pintype "unspecified"))
      (node (ref "USB") (pin "A12") (pinfunction "GND_A12") (pintype "unspecified"))
      (node (ref "USB") (pin "B12") (pinfunction "GND_B12") (pintype "unspecified"))
      (node (ref "USB1") (pin "7") (pinfunction "EH_7") (pintype "unspecified"))
      (node (ref "USB1") (pin "A12") (pinfunction "GND_A12") (pintype "unspecified"))
      (node (ref "USB1") (pin "B12") (pinfunction "GND_B12") (pintype "unspecified"))
      (node (ref "USB2") (pin "1") (pinfunction "GND_1") (pintype "unspecified"))
      (node (ref "USB2") (pin "12") (pinfunction "GND_12") (pintype "unspecified"))
      (node (ref "USB2") (pin "13") (pinfunction "SHELL_13") (pintype "unspecified"))
      (node (ref "USB2") (pin "14") (pinfunction "SHELL_14") (pintype "unspecified"))
      (node (ref "USB3") (pin "1") (pinfunction "GND_1") (pintype "unspecified"))
      (node (ref "USB3") (pin "12") (pinfunction "GND_12") (pintype "unspecified"))
      (node (ref "USB3") (pin "13") (pinfunction "SHELL_13") (pintype "unspecified"))
      (node (ref "USB3") (pin "14") (pinfunction "SHELL_14") (pintype "unspecified"))
    )
    (net (code "31") (name "Net-(LED1-K)") (class "Default")
      (node (ref "LED1") (pin "1") (pinfunction "K_1") (pintype "unspecified"))
      (node (ref "R2") (pin "1") (pinfunction "1_1") (pintype "input"))
    )
    (net (code "32") (name "Net-(LED2-A)") (class "Default")
      (node (ref "LED2") (pin "2") (pinfunction "A_2") (pintype "unspecified"))
      (node (ref "LED3") (pin "2") (pinfunction "A_2") (pintype "unspecified"))
      (node (ref "LED4") (pin "2") (pinfunction "A_2") (pintype "unspecified"))
      (node (ref "LED5") (pin "2") (pinfunction "A_2") (pintype "unspecified"))
      (node (ref "R3") (pin "1") (pinfunction "1_1") (pintype "input"))
    )
    (net (code "33") (name "Net-(LED6-A)") (class "Default")
      (node (ref "LED6") (pin "2") (pinfunction "A_2") (pintype "unspecified"))
      (node (ref "LED7") (pin "2") (pinfunction "A_2") (pintype "unspecified"))
      (node (ref "LED8") (pin "2") (pinfunction "A_2") (pintype "unspecified"))
      (node (ref "LED9") (pin "2") (pinfunction "A_2") (pintype "unspecified"))
      (node (ref "R4") (pin "1") (pinfunction "1_1") (pintype "input"))
    )
    (net (code "34") (name "Net-(LED10-A)") (class "Default")
      (node (ref "LED10") (pin "2") (pinfunction "A_2") (pintype "unspecified"))
      (node (ref "LED11") (pin "2") (pinfunction "A_2") (pintype "unspecified"))
      (node (ref "LED12") (pin "2") (pinfunction "A_2") (pintype "unspecified"))
      (node (ref "LED13") (pin "2") (pinfunction "A_2") (pintype "unspecified"))
      (node (ref "R5") (pin "1") (pinfunction "1_1") (pintype "input"))
    )
    (net (code "35") (name "Net-(LED14-A)") (class "Default")
      (node (ref "LED14") (pin "2") (pinfunction "A_2") (pintype "unspecified"))
      (node (ref "LED15") (pin "2") (pinfunction "A_2") (pintype "unspecified"))
      (node (ref "LED16") (pin "2") (pinfunction "A_2") (pintype "unspecified"))
      (node (ref "LED17") (pin "2") (pinfunction "A_2") (pintype "unspecified"))
      (node (ref "R6") (pin "1") (pinfunction "1_1") (pintype "input"))
    )
    (net (code "36") (name "Net-(LED18-A)") (class "Default")
      (node (ref "LED18") (pin "2") (pinfunction "A_2") (pintype "unspecified"))
      (node (ref "LED19") (pin "2") (pinfunction "A_2") (pintype "unspecified"))
      (node (ref "LED20") (pin "2") (pinfunction "A_2") (pintype "unspecified"))
      (node (ref "LED21") (pin "2") (pinfunction "A_2") (pintype "unspecified"))
      (node (ref "R7") (pin "1") (pinfunction "1_1") (pintype "input"))
    )
    (net (code "37") (name "Net-(LED22-DOUT)") (class "Default")
      (node (ref "LED22") (pin "3") (pinfunction "DOUT_3") (pintype "unspecified"))
      (node (ref "LED23") (pin "1") (pinfunction "DIN_1") (pintype "unspecified"))
    )
    (net (code "38") (name "Net-(LED24-A)") (class "Default")
      (node (ref "LED24") (pin "2") (pinfunction "A_2") (pintype "unspecified"))
      (node (ref "R17") (pin "1") (pinfunction "1_1") (pintype "input"))
    )
    (net (code "39") (name "Net-(LED25-A)") (class "Default")
      (node (ref "LED25") (pin "2") (pinfunction "A_2") (pintype "unspecified"))
      (node (ref "R18") (pin "1") (pinfunction "1_1") (pintype "input"))
    )
    (net (code "40") (name "Net-(LED26-A)") (class "Default")
      (node (ref "LED26") (pin "2") (pinfunction "A_2") (pintype "unspecified"))
      (node (ref "R19") (pin "1") (pinfunction "1_1") (pintype "input"))
    )
    (net (code "41") (name "Net-(LED28-A)") (class "Default")
      (node (ref "LED28") (pin "2") (pinfunction "A_2") (pintype "unspecified"))
      (node (ref "R22") (pin "1") (pinfunction "1_1") (pintype "input"))
    )
    (net (code "42") (name "Net-(LED29-A)") (class "Default")
      (node (ref "LED29") (pin "2") (pinfunction "A_2") (pintype "unspecified"))
      (node (ref "R25") (pin "1") (pinfunction "1_1") (pintype "input"))
    )
    (net (code "43") (name "Net-(LED30-A)") (class "Default")
      (node (ref "LED30") (pin "2") (pinfunction "A_2") (pintype "unspecified"))
      (node (ref "R26") (pin "1") (pinfunction "1_1") (pintype "input"))
    )
    (net (code "44") (name "Net-(U1-PD7)") (class "Default")
      (node (ref "R1") (pin "1") (pinfunction "1_1") (pintype "input"))
      (node (ref "SW1") (pin "3") (pinfunction "3_3") (pintype "input"))
      (node (ref "SW1") (pin "4") (pinfunction "4_4") (pintype "input"))
      (node (ref "U1") (pin "1") (pinfunction "PD7_1") (pintype "unspecified"))
    )
    (net (code "45") (name "Net-(U4-TNOW)") (class "Default")
      (node (ref "R19") (pin "2") (pinfunction "2_2") (pintype "input"))
      (node (ref "U4") (pin "6") (pinfunction "TNOW_6") (pintype "unspecified"))
    )
    (net (code "46") (name "Net-(U4-TXD)") (class "Default")
      (node (ref "R20") (pin "2") (pinfunction "2_2") (pintype "input"))
      (node (ref "U4") (pin "8") (pinfunction "TXD_8") (pintype "unspecified"))
    )
    (net (code "47") (name "Net-(U7-RXD)") (class "Default")
      (node (ref "R24") (pin "2") (pinfunction "2_2") (pintype "input"))
      (node (ref "U7") (pin "9") (pinfunction "RXD_9") (pintype "unspecified"))
    )
    (net (code "48") (name "Net-(U7-TNOW)") (class "Default")
      (node (ref "R22") (pin "2") (pinfunction "2_2") (pintype "input"))
      (node (ref "U7") (pin "6") (pinfunction "TNOW_6") (pintype "unspecified"))
    )
    (net (code "49") (name "Net-(U7-TXD)") (class "Default")
      (node (ref "R23") (pin "2") (pinfunction "2_2") (pintype "input"))
      (node (ref "U7") (pin "8") (pinfunction "TXD_8") (pintype "unspecified"))
    )
    (net (code "50") (name "Net-(USB-CC1)") (class "Default")
      (node (ref "R12") (pin "2") (pinfunction "2_2") (pintype "input"))
      (node (ref "USB") (pin "A5") (pinfunction "CC1_A5") (pintype "unspecified"))
    )
    (net (code "51") (name "Net-(USB-CC2)") (class "Default")
      (node (ref "R11") (pin "2") (pinfunction "2_2") (pintype "input"))
      (node (ref "USB") (pin "B5") (pinfunction "CC2_B5") (pintype "unspecified"))
    )
    (net (code "52") (name "Net-(USB1-CC1)") (class "Default")
      (node (ref "R8") (pin "2") (pinfunction "2_2") (pintype "input"))
      (node (ref "USB1") (pin "A5") (pinfunction "CC1_A5") (pintype "unspecified"))
    )
    (net (code "53") (name "Net-(USB1-CC2)") (class "Default")
      (node (ref "R9") (pin "2") (pinfunction "2_2") (pintype "input"))
      (node (ref "USB1") (pin "B5") (pinfunction "CC2_B5") (pintype "unspecified"))
    )
    (net (code "54") (name "Net-(USB2-CC1)") (class "Default")
      (node (ref "R13") (pin "2") (pinfunction "2_2") (pintype "input"))
      (node (ref "USB2") (pin "4") (pinfunction "CC1_4") (pintype "unspecified"))
    )
    (net (code "55") (name "Net-(USB2-CC2)") (class "Default")
      (node (ref "R14") (pin "2") (pinfunction "2_2") (pintype "input"))
      (node (ref "USB2") (pin "10") (pinfunction "CC2_10") (pintype "unspecified"))
    )
    (net (code "56") (name "Net-(USB3-CC1)") (class "Default")
      (node (ref "R15") (pin "2") (pinfunction "2_2") (pintype "input"))
      (node (ref "USB3") (pin "4") (pinfunction "CC1_4") (pintype "unspecified"))
    )
    (net (code "57") (name "Net-(USB3-CC2)") (class "Default")
      (node (ref "R16") (pin "2") (pinfunction "2_2") (pintype "input"))
      (node (ref "USB3") (pin "10") (pinfunction "CC2_10") (pintype "unspecified"))
    )
    (net (code "58") (name "VBUS") (class "Default")
      (node (ref "C10") (pin "1") (pinfunction "1_1") (pintype "input"))
      (node (ref "C9") (pin "2") (pinfunction "2_2") (pintype "input"))
      (node (ref "R17") (pin "2") (pinfunction "2_2") (pintype "input"))
      (node (ref "SW3") (pin "3") (pinfunction "3_3") (pintype "unspecified"))
      (node (ref "U6") (pin "1") (pinfunction "IN_1") (pintype "unspecified"))
      (node (ref "U6") (pin "3") (pinfunction "EN_3") (pintype "unspecified"))
      (node (ref "USB3") (pin "11") (pinfunction "VBUS_11") (pintype "unspecified"))
      (node (ref "USB3") (pin "2") (pinfunction "VBUS_2") (pintype "unspecified"))
    )
    (net (code "59") (name "VDD.P") (class "Default")
      (node (ref "C12") (pin "2") (pinfunction "2_2") (pintype "input"))
      (node (ref "C13") (pin "2") (pinfunction "2_2") (pintype "input"))
      (node (ref "SW3") (pin "2") (pinfunction "2_2") (pintype "unspecified"))
      (node (ref "U4") (pin "7") (pinfunction "VCC_7") (pintype "unspecified"))
      (node (ref "U7") (pin "7") (pinfunction "VCC_7") (pintype "unspecified"))
    )
    (net (code "60") (name "VIN") (class "Default")
      (node (ref "C2") (pin "1") (pinfunction "1_1") (pintype "input"))
      (node (ref "C3") (pin "2") (pinfunction "2_2") (pintype "input"))
      (node (ref "D1") (pin "2") (pinfunction "2_2") (pintype "unspecified"))
      (node (ref "U2") (pin "1") (pinfunction "VIN_1") (pintype "unspecified"))
      (node (ref "U2") (pin "3") (pinfunction "Shutdown#_3") (pintype "unspecified"))
      (node (ref "USB1") (pin "A9") (pinfunction "VBUS_A9") (pintype "unspecified"))
      (node (ref "USB1") (pin "B9") (pinfunction "VBUS_B9") (pintype "unspecified"))
    )
    (net (code "61") (name "unconnected-(LED23-DOUT-Pad3)") (class "Default")
      (node (ref "LED23") (pin "3") (pinfunction "DOUT_3") (pintype "unspecified+no_connect"))
    )
    (net (code "62") (name "unconnected-(SW1-Pad5)") (class "Default")
      (node (ref "SW1") (pin "5") (pinfunction "5_5") (pintype "input+no_connect"))
    )
    (net (code "63") (name "unconnected-(SW1-Pad6)") (class "Default")
      (node (ref "SW1") (pin "6") (pinfunction "6_6") (pintype "input+no_connect"))
    )
    (net (code "64") (name "unconnected-(SW2-Pad5)") (class "Default")
      (node (ref "SW2") (pin "5") (pinfunction "5_5") (pintype "input+no_connect"))
    )
    (net (code "65") (name "unconnected-(SW2-Pad6)") (class "Default")
      (node (ref "SW2") (pin "6") (pinfunction "6_6") (pintype "input+no_connect"))
    )
    (net (code "66") (name "unconnected-(U2-NC{slash}ADJ-Pad4)") (class "Default")
      (node (ref "U2") (pin "4") (pinfunction "NC/ADJ_4") (pintype "unspecified+no_connect"))
    )
    (net (code "67") (name "unconnected-(U3-PA1-Pad20)") (class "Default")
      (node (ref "U3") (pin "20") (pinfunction "PA1_20") (pintype "unspecified+no_connect"))
    )
    (net (code "68") (name "unconnected-(U3-PA2-Pad1)") (class "Default")
      (node (ref "U3") (pin "1") (pinfunction "PA2_1") (pintype "unspecified+no_connect"))
    )
    (net (code "69") (name "unconnected-(U3-PA4-Pad5)") (class "Default")
      (node (ref "U3") (pin "5") (pinfunction "PA4_5") (pintype "unspecified+no_connect"))
    )
    (net (code "70") (name "unconnected-(U3-PA5-Pad6)") (class "Default")
      (node (ref "U3") (pin "6") (pinfunction "PA5_6") (pintype "unspecified+no_connect"))
    )
    (net (code "71") (name "unconnected-(U3-PA7-Pad8)") (class "Default")
      (node (ref "U3") (pin "8") (pinfunction "PA7_8") (pintype "unspecified+no_connect"))
    )
    (net (code "72") (name "unconnected-(U3-PB3{slash}TOSC1-Pad11)") (class "Default")
      (node (ref "U3") (pin "11") (pinfunction "PB3/TOSC1_11") (pintype "unspecified+no_connect"))
    )
    (net (code "73") (name "unconnected-(U3-PB4-Pad10)") (class "Default")
      (node (ref "U3") (pin "10") (pinfunction "PB4_10") (pintype "unspecified+no_connect"))
    )
    (net (code "74") (name "unconnected-(U3-PB5-Pad9)") (class "Default")
      (node (ref "U3") (pin "9") (pinfunction "PB5_9") (pintype "unspecified+no_connect"))
    )
    (net (code "75") (name "unconnected-(U3-PC0-Pad15)") (class "Default")
      (node (ref "U3") (pin "15") (pinfunction "PC0_15") (pintype "unspecified+no_connect"))
    )
    (net (code "76") (name "unconnected-(U3-PC1-Pad16)") (class "Default")
      (node (ref "U3") (pin "16") (pinfunction "PC1_16") (pintype "unspecified+no_connect"))
    )
    (net (code "77") (name "unconnected-(U3-PC2-Pad17)") (class "Default")
      (node (ref "U3") (pin "17") (pinfunction "PC2_17") (pintype "unspecified+no_connect"))
    )
    (net (code "78") (name "unconnected-(U3-PC3-Pad18)") (class "Default")
      (node (ref "U3") (pin "18") (pinfunction "PC3_18") (pintype "unspecified+no_connect"))
    )
    (net (code "79") (name "unconnected-(U4-CTS#-Pad5)") (class "Default")
      (node (ref "U4") (pin "5") (pinfunction "CTS#_5") (pintype "unspecified+no_connect"))
    )
    (net (code "80") (name "unconnected-(U4-RTS#-Pad4)") (class "Default")
      (node (ref "U4") (pin "4") (pinfunction "RTS#_4") (pintype "unspecified+no_connect"))
    )
    (net (code "81") (name "unconnected-(U6-NC-Pad4)") (class "Default")
      (node (ref "U6") (pin "4") (pinfunction "NC_4") (pintype "unspecified+no_connect"))
    )
    (net (code "82") (name "unconnected-(U7-CTS#-Pad5)") (class "Default")
      (node (ref "U7") (pin "5") (pinfunction "CTS#_5") (pintype "unspecified+no_connect"))
    )
    (net (code "83") (name "unconnected-(U7-RTS#-Pad4)") (class "Default")
      (node (ref "U7") (pin "4") (pinfunction "RTS#_4") (pintype "unspecified+no_connect"))
    )
    (net (code "84") (name "unconnected-(USB2-SBU1-Pad9)") (class "Default")
      (node (ref "USB2") (pin "9") (pinfunction "SBU1_9") (pintype "unspecified+no_connect"))
    )
    (net (code "85") (name "unconnected-(USB2-SBU2-Pad3)") (class "Default")
      (node (ref "USB2") (pin "3") (pinfunction "SBU2_3") (pintype "unspecified+no_connect"))
    )
    (net (code "86") (name "unconnected-(USB2-VBUS-Pad2)") (class "Default")
      (node (ref "USB2") (pin "2") (pinfunction "VBUS_2") (pintype "unspecified+no_connect"))
    )
    (net (code "87") (name "unconnected-(USB2-VBUS-Pad11)") (class "Default")
      (node (ref "USB2") (pin "11") (pinfunction "VBUS_11") (pintype "unspecified+no_connect"))
    )
    (net (code "88") (name "unconnected-(USB3-SBU1-Pad9)") (class "Default")
      (node (ref "USB3") (pin "9") (pinfunction "SBU1_9") (pintype "unspecified+no_connect"))
    )
    (net (code "89") (name "unconnected-(USB3-SBU2-Pad3)") (class "Default")
      (node (ref "USB3") (pin "3") (pinfunction "SBU2_3") (pintype "unspecified+no_connect"))
    )
  )
)
